# 2_power_supply.net
KiCad netlist of a schematic drawn in Altium Designer
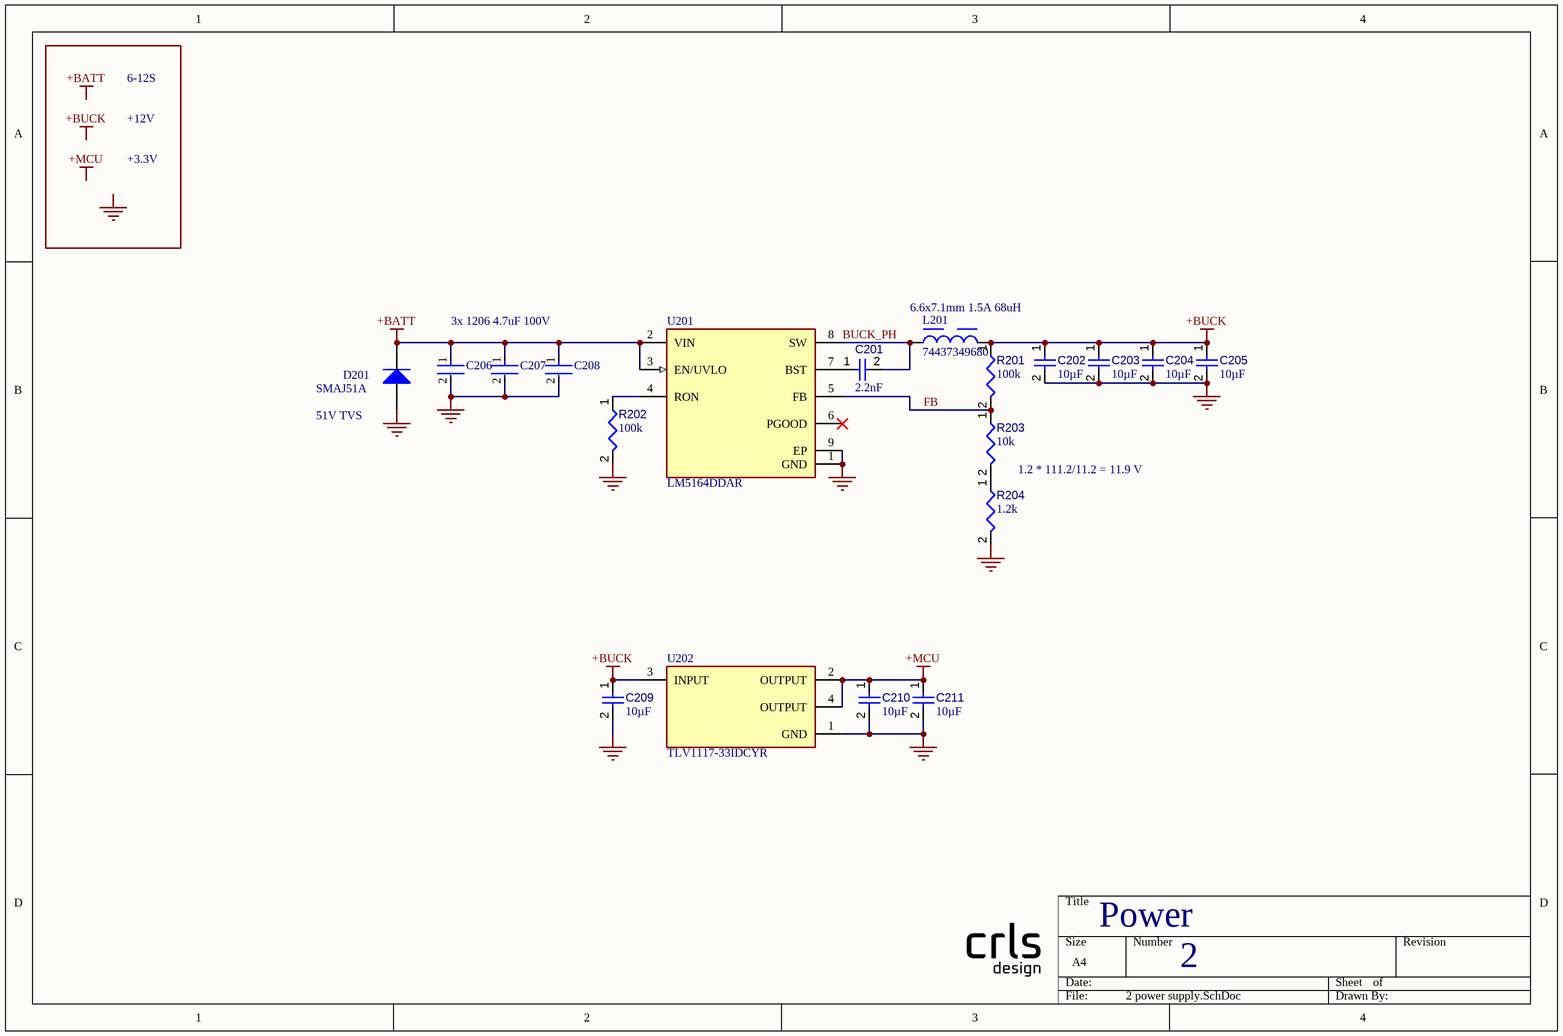
[diagram p0: 2 power supply.SchDoc]

(export (version "E")
  (design (tool "Eeschema 10.0.6"))
  (components
    (comp (ref "C201")
      (value "2.2nF")
      (footprint "CAPC0402(1005)33_L")
      (description "Chip Capacitor, 1nF +/-20%, 50V, 0402, Thickness 0.33 mm")
      (fields (field (name "TOLERANCE") "10%") (field (name "Comment") "Capacitor 2.2nF +/-20% 50V 0402"))
      (libsource (lib "UBC Uncrewed Aircraft Systems") (part "CAP-NP-2"))
    )
    (comp (ref "C202")
      (value "10µF")
      (footprint "CAPC0603(1608)100_L")
      (description "Chip Capacitor, 10µF +/-20%, 10V, 0603, Thickness 1 mm")
      (fields (field (name "TOLERANCE") "10%") (field (name "Comment") "Capacitor 10µF +/-20% 10V 0603"))
      (libsource (lib "UBC Uncrewed Aircraft Systems") (part "CAP-NP-2"))
    )
    (comp (ref "C203")
      (value "10µF")
      (footprint "CAPC0603(1608)100_L")
      (description "Chip Capacitor, 10µF +/-20%, 10V, 0603, Thickness 1 mm")
      (fields (field (name "TOLERANCE") "10%") (field (name "Comment") "Capacitor 10µF +/-20% 10V 0603"))
      (libsource (lib "UBC Uncrewed Aircraft Systems") (part "CAP-NP-2"))
    )
    (comp (ref "C204")
      (value "10µF")
      (footprint "CAPC0603(1608)100_L")
      (description "Chip Capacitor, 10µF +/-20%, 10V, 0603, Thickness 1 mm")
      (fields (field (name "TOLERANCE") "10%") (field (name "Comment") "Capacitor 10µF +/-20% 10V 0603"))
      (libsource (lib "UBC Uncrewed Aircraft Systems") (part "CAP-NP-2"))
    )
    (comp (ref "C205")
      (value "10µF")
      (footprint "CAPC0603(1608)100_L")
      (description "Chip Capacitor, 10µF +/-20%, 10V, 0603, Thickness 1 mm")
      (fields (field (name "TOLERANCE") "10%") (field (name "Comment") "Capacitor 10µF +/-20% 10V 0603"))
      (libsource (lib "UBC Uncrewed Aircraft Systems") (part "CAP-NP-2"))
    )
    (comp (ref "C206")
      (value "12061Z475KAT2A")
      (footprint "FP-1206-L_3_2_0_2-W_1_6_0-MFG")
      (description "CAP CER 4.7UF 100V X7S 1206")
      (fields (field (name "TOLERANCE") "10%"))
      (libsource (lib "Altium Content Vault") (part "b4654b650e69147ec39a6b967a45e02"))
    )
    (comp (ref "C207")
      (value "12061Z475KAT2A")
      (footprint "FP-1206-L_3_2_0_2-W_1_6_0-MFG")
      (description "CAP CER 4.7UF 100V X7S 1206")
      (fields (field (name "TOLERANCE") "10%"))
      (libsource (lib "Altium Content Vault") (part "b4654b650e69147ec39a6b967a45e02"))
    )
    (comp (ref "C208")
      (value "12061Z475KAT2A")
      (footprint "FP-1206-L_3_2_0_2-W_1_6_0-MFG")
      (description "CAP CER 4.7UF 100V X7S 1206")
      (fields (field (name "TOLERANCE") "10%"))
      (libsource (lib "Altium Content Vault") (part "b4654b650e69147ec39a6b967a45e02"))
    )
    (comp (ref "C209")
      (value "10µF")
      (footprint "CAPC0603(1608)100_L")
      (description "Chip Capacitor, 10µF +/-20%, 10V, 0603, Thickness 1 mm")
      (fields (field (name "TOLERANCE") "10%") (field (name "Comment") "Capacitor 10µF +/-20% 10V 0603"))
      (libsource (lib "UBC Uncrewed Aircraft Systems") (part "CAP-NP-2"))
    )
    (comp (ref "C210")
      (value "10µF")
      (footprint "CAPC0603(1608)100_L")
      (description "Chip Capacitor, 10µF +/-20%, 10V, 0603, Thickness 1 mm")
      (fields (field (name "TOLERANCE") "10%") (field (name "Comment") "Capacitor 10µF +/-20% 10V 0603"))
      (libsource (lib "UBC Uncrewed Aircraft Systems") (part "CAP-NP-2"))
    )
    (comp (ref "C211")
      (value "10µF")
      (footprint "CAPC0603(1608)100_L")
      (description "Chip Capacitor, 10µF +/-20%, 10V, 0603, Thickness 1 mm")
      (fields (field (name "TOLERANCE") "10%") (field (name "Comment") "Capacitor 10µF +/-20% 10V 0603"))
      (libsource (lib "UBC Uncrewed Aircraft Systems") (part "CAP-NP-2"))
    )
    (comp (ref "D201")
      (value "SMAJ51A")
      (footprint "VISH-DO-214AC-2_N")
      (fields
        (field (name "MANUFACTURER") "Vishay Semiconductor")
        (field (name "PARTNUMBER") "SMAJ51A-E3/5A")
      )
      (libsource (lib "Altium Content Vault") (part "VISH-K1A2-2"))
    )
    (comp (ref "L201")
      (value "74437349680")
      (footprint "WE-LHMI_7050")
      (libsource (lib "Altium Content Vault") (part "Inductor - 3"))
    )
    (comp (ref "R201")
      (value "100k")
      (footprint "RESC0402(1005)_L")
      (description "Chip Resistor, 100 kOhms, +/-1 %, 63 mW, -55 to 155 degC, 0402")
      (fields (field (name "TOLERANCE") "1%") (field (name "POWER") "63mW"))
      (libsource (lib "UBC Uncrewed Aircraft Systems") (part "RES-2"))
    )
    (comp (ref "R202")
      (value "100k")
      (footprint "RESC0402(1005)_L")
      (description "Chip Resistor, 100 kOhms, +/-1 %, 63 mW, -55 to 155 degC, 0402")
      (fields (field (name "TOLERANCE") "1%") (field (name "POWER") "63mW"))
      (libsource (lib "UBC Uncrewed Aircraft Systems") (part "RES-2"))
    )
    (comp (ref "R203")
      (value "10k")
      (footprint "RESC0402(1005)_L")
      (description "Chip Resistor, 10 kOhms, +/-1 %, 63 mW, -55 to 125 degC, 0402")
      (fields (field (name "POWER") "63mW") (field (name "TOLERANCE") "1%"))
      (libsource (lib "UBC Uncrewed Aircraft Systems") (part "RES-2"))
    )
    (comp (ref "R204")
      (value "1.2k")
      (footprint "RESC0402(1005)_L")
      (description "Chip Resistor, 1.2 kOhms, +/-1 %, 63 mW, -55 to 155 degC, 0402")
      (fields (field (name "TOLERANCE") "1%") (field (name "POWER") "63mW"))
      (libsource (lib "UBC Uncrewed Aircraft Systems") (part "RES-2"))
    )
    (comp (ref "U201")
      (value "LM5164DDAR")
      (footprint "FP-DDA0008E-MFG")
      (description "POWER MANAGEMENT")
      (fields
        (field (name "MANUFACTURER") "Texas Instruments")
        (field (name "OCTOPART") "https://octopart.com/lm5164ddar-texas+instruments-96785744")
      )
      (libsource (lib "Altium Content Vault") (part "ad4762e8767f3654d2dc1ed5c3dee12"))
    )
    (comp (ref "U202")
      (value "TLV1117-33IDCYR")
      (footprint "FP-DCY0004A-MFG")
      (description "IC REG LIN 3.3V 800MA SOT223-4")
      (fields
        (field (name "MANUFACTURER") "Texas Instruments")
        (field (name "OCTOPART") "https://octopart.com/tlv1117-33idcyr-texas+instruments-669250")
      )
      (libsource (lib "Altium Content Vault") (part "d420fb9686013fb832e66295cdf4acf"))
    )
  )
  (nets
    (net (code "1") (name "+BATT") (class "Default")
      (node (ref "C206") (pin "1") (pinfunction "1_1") (pintype "passive"))
      (node (ref "C207") (pin "1") (pinfunction "1_1") (pintype "passive"))
      (node (ref "C208") (pin "1") (pinfunction "1_1") (pintype "passive"))
      (node (ref "D201") (pin "1") (pinfunction "K_1") (pintype "passive"))
      (node (ref "U201") (pin "2") (pinfunction "VIN_2") (pintype "power_in"))
      (node (ref "U201") (pin "3") (pinfunction "EN/UVLO_3") (pintype "input"))
    )
    (net (code "2") (name "+BUCK") (class "Default")
      (node (ref "C202") (pin "1") (pinfunction "1_1") (pintype "passive"))
      (node (ref "C203") (pin "1") (pinfunction "1_1") (pintype "passive"))
      (node (ref "C204") (pin "1") (pinfunction "1_1") (pintype "passive"))
      (node (ref "C205") (pin "1") (pinfunction "1_1") (pintype "passive"))
      (node (ref "C209") (pin "1") (pinfunction "1_1") (pintype "passive"))
      (node (ref "L201") (pin "2") (pinfunction "2_2") (pintype "passive"))
      (node (ref "R201") (pin "1") (pinfunction "1_1") (pintype "passive"))
      (node (ref "U202") (pin "3") (pinfunction "INPUT_3") (pintype "power_in"))
    )
    (net (code "3") (name "+MCU") (class "Default")
      (node (ref "C210") (pin "1") (pinfunction "1_1") (pintype "passive"))
      (node (ref "C211") (pin "1") (pinfunction "1_1") (pintype "passive"))
      (node (ref "U202") (pin "2") (pinfunction "OUTPUT_2") (pintype "power_in"))
      (node (ref "U202") (pin "4") (pinfunction "OUTPUT_4") (pintype "power_in"))
    )
    (net (code "4") (name "/BUCK_PH") (class "Default")
      (node (ref "C201") (pin "2") (pinfunction "2_2") (pintype "passive"))
      (node (ref "L201") (pin "1") (pinfunction "1_1") (pintype "passive"))
      (node (ref "U201") (pin "8") (pinfunction "SW_8") (pintype "passive"))
    )
    (net (code "5") (name "/FB") (class "Default")
      (node (ref "R201") (pin "2") (pinfunction "2_2") (pintype "passive"))
      (node (ref "R203") (pin "1") (pinfunction "1_1") (pintype "passive"))
      (node (ref "U201") (pin "5") (pinfunction "FB_5") (pintype "passive"))
    )
    (net (code "6") (name "GND") (class "Default")
      (node (ref "C202") (pin "2") (pinfunction "2_2") (pintype "passive"))
      (node (ref "C203") (pin "2") (pinfunction "2_2") (pintype "passive"))
      (node (ref "C204") (pin "2") (pinfunction "2_2") (pintype "passive"))
      (node (ref "C205") (pin "2") (pinfunction "2_2") (pintype "passive"))
      (node (ref "C206") (pin "2") (pinfunction "2_2") (pintype "passive"))
      (node (ref "C207") (pin "2") (pinfunction "2_2") (pintype "passive"))
      (node (ref "C208") (pin "2") (pinfunction "2_2") (pintype "passive"))
      (node (ref "C209") (pin "2") (pinfunction "2_2") (pintype "passive"))
      (node (ref "C210") (pin "2") (pinfunction "2_2") (pintype "passive"))
      (node (ref "C211") (pin "2") (pinfunction "2_2") (pintype "passive"))
      (node (ref "D201") (pin "2") (pinfunction "A_2") (pintype "passive"))
      (node (ref "R202") (pin "2") (pinfunction "2_2") (pintype "passive"))
      (node (ref "R204") (pin "2") (pinfunction "2_2") (pintype "passive"))
      (node (ref "U201") (pin "1") (pinfunction "GND_1") (pintype "power_in"))
      (node (ref "U201") (pin "9") (pinfunction "EP_9") (pintype "passive"))
      (node (ref "U202") (pin "1") (pinfunction "GND_1") (pintype "power_in"))
    )
    (net (code "7") (name "Net-(R203-Pad2)") (class "Default")
      (node (ref "R203") (pin "2") (pinfunction "2_2") (pintype "passive"))
      (node (ref "R204") (pin "1") (pinfunction "1_1") (pintype "passive"))
    )
    (net (code "8") (name "Net-(U201-BST)") (class "Default")
      (node (ref "C201") (pin "1") (pinfunction "1_1") (pintype "passive"))
      (node (ref "U201") (pin "7") (pinfunction "BST_7") (pintype "passive"))
    )
    (net (code "9") (name "Net-(U201-RON)") (class "Default")
      (node (ref "R202") (pin "1") (pinfunction "1_1") (pintype "passive"))
      (node (ref "U201") (pin "4") (pinfunction "RON_4") (pintype "passive"))
    )
    (net (code "10") (name "unconnected-(U201-PGOOD-Pad6)") (class "Default")
      (node (ref "U201") (pin "6") (pinfunction "PGOOD_6") (pintype "open_collector+no_connect"))
    )
  )
)
